# 2022-LC-MNT-3.net
KiCad netlist of a schematic drawn in EasyEDA Pro
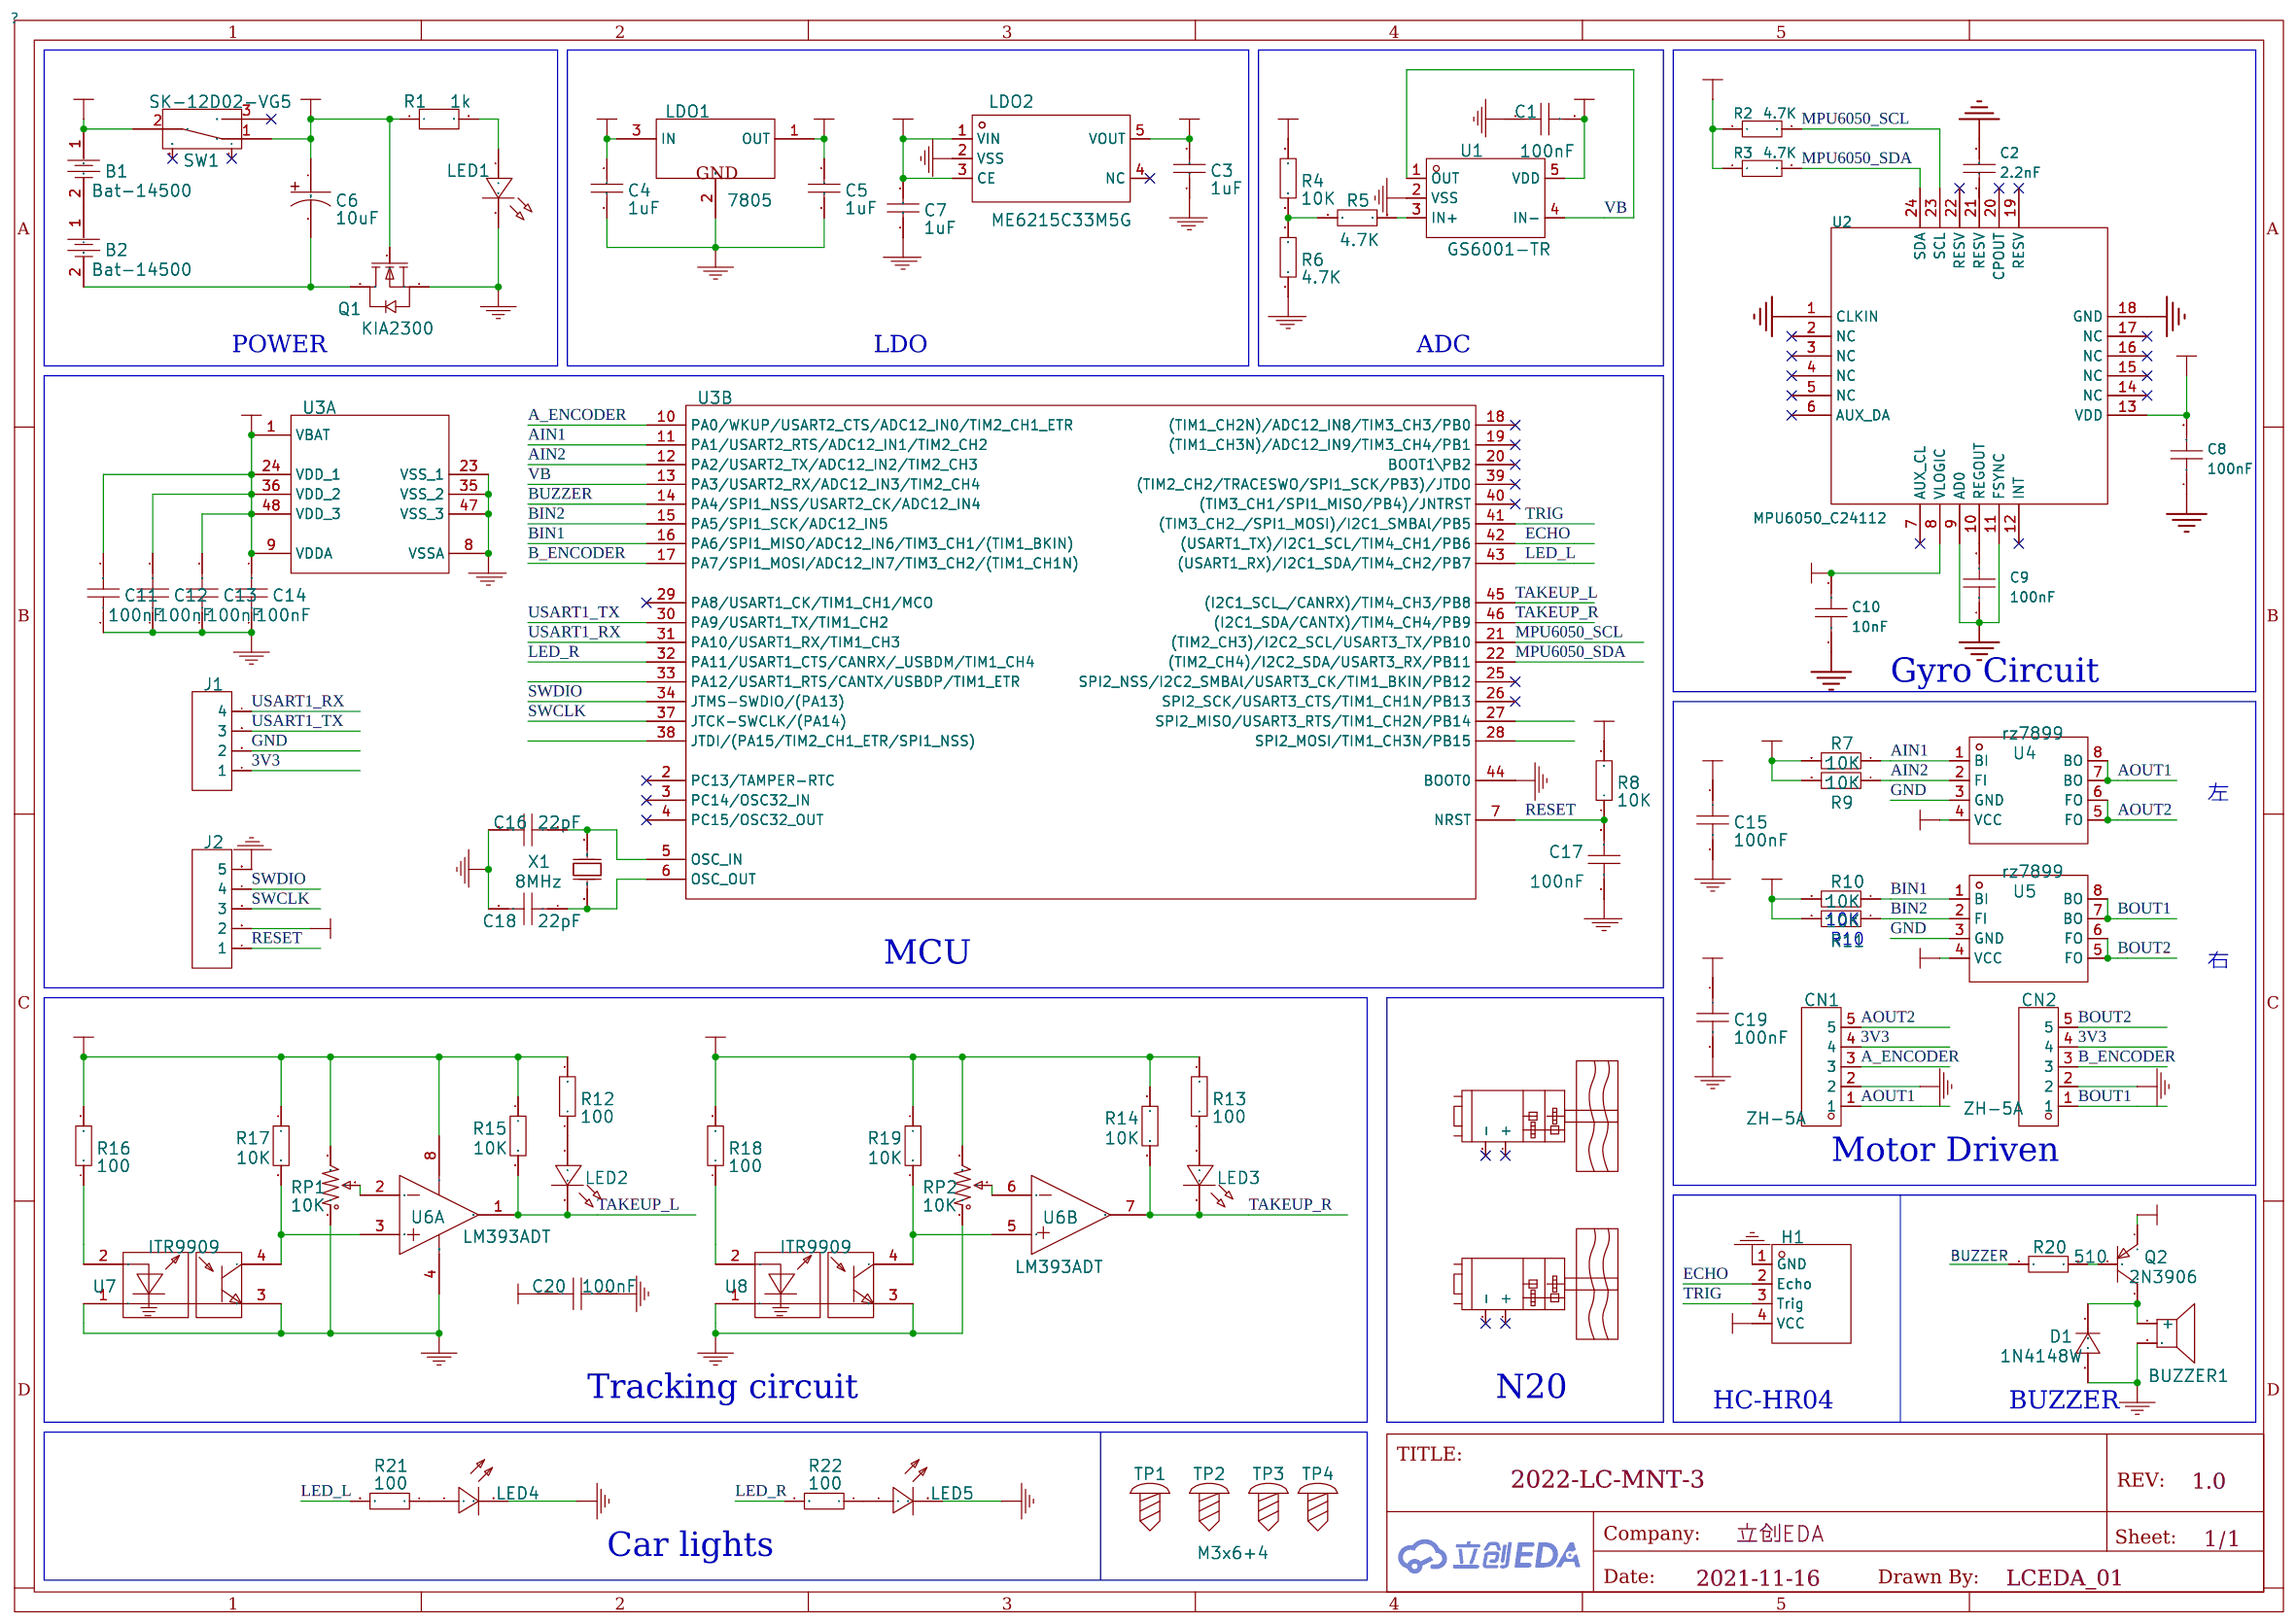
[diagram p0: schematic sheet]

(export (version "E")
  (design (tool "Eeschema 10.0.6"))
  (components
    (comp (ref "ASS_1") (value "直流电机N20") (libsource (lib "easyedapro") (part "直流电机N20")))
    (comp (ref "ASS_2") (value "直流电机N20") (libsource (lib "easyedapro") (part "直流电机N20")))
    (comp (ref "B1") (value "Bat-14500") (libsource (lib "easyedapro") (part "Bat-14500")))
    (comp (ref "B2") (value "Bat-14500") (libsource (lib "easyedapro") (part "Bat-14500")))
    (comp (ref "BUZZER1")
      (value "TMB12A12")
      (fields (field (name "Manufacturer") "HNDZ"))
      (libsource (lib "easyedapro") (part "TMB12A12"))
    )
    (comp (ref "C1")
      (value "100nF")
      (fields (field (name "Manufacturer Part") "CC0603KRX7R9BB104") (field (name "Manufacturer") "YAGEO"))
      (libsource (lib "") (part "100nF_1"))
    )
    (comp (ref "C2") (value "2.2nF") (libsource (lib "easyedapro") (part "2.2nF")))
    (comp (ref "C3")
      (value "1uF")
      (fields (field (name "Manufacturer Part") "CC0603KRX5R8BB105") (field (name "Manufacturer") "YAGEO"))
      (libsource (lib "easyedapro") (part "1uF"))
    )
    (comp (ref "C4")
      (value "1uF")
      (fields (field (name "Manufacturer Part") "CC0603KRX5R8BB105") (field (name "Manufacturer") "YAGEO"))
      (libsource (lib "easyedapro") (part "1uF"))
    )
    (comp (ref "C5")
      (value "1uF")
      (fields (field (name "Manufacturer Part") "CC0603KRX5R8BB105") (field (name "Manufacturer") "YAGEO"))
      (libsource (lib "easyedapro") (part "1uF"))
    )
    (comp (ref "C6")
      (value "10uF")
      (fields (field (name "Manufacturer Part") "CA45-A-16V-10μF-K") (field (name "Manufacturer") "TORCH"))
      (libsource (lib "easyedapro") (part "10uF"))
    )
    (comp (ref "C7")
      (value "1uF")
      (fields (field (name "Manufacturer Part") "CC0603KRX5R8BB105") (field (name "Manufacturer") "YAGEO"))
      (libsource (lib "easyedapro") (part "1uF"))
    )
    (comp (ref "C8") (value "100nF") (libsource (lib "easyedapro") (part "100nF")))
    (comp (ref "C9") (value "100nF") (libsource (lib "easyedapro") (part "100nF")))
    (comp (ref "C10") (value "10nF") (libsource (lib "easyedapro") (part "10nF")))
    (comp (ref "C11")
      (value "100nF")
      (fields (field (name "Manufacturer Part") "CC0603KRX7R9BB104") (field (name "Manufacturer") "YAGEO"))
      (libsource (lib "") (part "100nF_1"))
    )
    (comp (ref "C12")
      (value "100nF")
      (fields (field (name "Manufacturer Part") "CC0603KRX7R9BB104") (field (name "Manufacturer") "YAGEO"))
      (libsource (lib "") (part "100nF_1"))
    )
    (comp (ref "C13")
      (value "100nF")
      (fields (field (name "Manufacturer Part") "CC0603KRX7R9BB104") (field (name "Manufacturer") "YAGEO"))
      (libsource (lib "") (part "100nF_1"))
    )
    (comp (ref "C14")
      (value "100nF")
      (fields (field (name "Manufacturer Part") "CC0603KRX7R9BB104") (field (name "Manufacturer") "YAGEO"))
      (libsource (lib "") (part "100nF_1"))
    )
    (comp (ref "C15")
      (value "100nF")
      (fields (field (name "Manufacturer Part") "CC0603KRX7R9BB104") (field (name "Manufacturer") "YAGEO"))
      (libsource (lib "") (part "100nF_1"))
    )
    (comp (ref "C16")
      (value "22pF")
      (fields (field (name "Manufacturer Part") "CC0603FRNPO9BN220") (field (name "Manufacturer") "YAGEO"))
      (libsource (lib "easyedapro") (part "22pF"))
    )
    (comp (ref "C17")
      (value "100nF")
      (fields (field (name "Manufacturer Part") "CC0603KRX7R9BB104") (field (name "Manufacturer") "YAGEO"))
      (libsource (lib "") (part "100nF_1"))
    )
    (comp (ref "C18")
      (value "22pF")
      (fields (field (name "Manufacturer Part") "CC0603FRNPO9BN220") (field (name "Manufacturer") "YAGEO"))
      (libsource (lib "easyedapro") (part "22pF"))
    )
    (comp (ref "C19")
      (value "100nF")
      (fields (field (name "Manufacturer Part") "CC0603KRX7R9BB104") (field (name "Manufacturer") "YAGEO"))
      (libsource (lib "") (part "100nF_1"))
    )
    (comp (ref "C20")
      (value "100nF")
      (fields (field (name "Manufacturer Part") "CC0603KRX7R9BB104") (field (name "Manufacturer") "YAGEO"))
      (libsource (lib "") (part "100nF_1"))
    )
    (comp (ref "CN1")
      (value "ZH-5A")
      (fields (field (name "Manufacturer") "BOOMELE"))
      (libsource (lib "easyedapro") (part "ZH-5A"))
    )
    (comp (ref "CN2")
      (value "ZH-5A")
      (fields (field (name "Manufacturer") "BOOMELE"))
      (libsource (lib "easyedapro") (part "ZH-5A"))
    )
    (comp (ref "D1")
      (value "1N4148W")
      (fields (field (name "Manufacturer") "Tak Cheong"))
      (libsource (lib "easyedapro") (part "1N4148W"))
    )
    (comp (ref "H1") (value "超声波测距模块_HC-HR04") (libsource (lib "easyedapro") (part "超声波测距模块_HC-HR04")))
    (comp (ref "J1") (value "HDR-M-2.54_1x4") (libsource (lib "easyedapro") (part "HDR-M-2.54_1x4")))
    (comp (ref "J2") (value "HDR-M-2.54_1x5") (libsource (lib "easyedapro") (part "HDR-M-2.54_1x5")))
    (comp (ref "LDO1")
      (value "7805")
      (fields (field (name "Manufacturer Part") "CJ78L05") (field (name "Manufacturer") "CJ"))
      (libsource (lib "easyedapro") (part "7805"))
    )
    (comp (ref "LDO2")
      (value "ME6215C33M5G")
      (fields (field (name "Manufacturer") "MICRONE"))
      (libsource (lib "easyedapro") (part "ME6215C33M5G"))
    )
    (comp (ref "LED1")
      (value "LED-0603_R")
      (fields
        (field (name "Manufacturer Part") "19-217/R6C-AL1M2VY/3T")
        (field (name "Manufacturer") "EVERLIGHT(台湾亿光)")
      )
      (libsource (lib "easyedapro") (part "LED-0603_R"))
    )
    (comp (ref "LED2")
      (value "LED-0805_G")
      (fields (field (name "Manufacturer Part") "NCD0805G1") (field (name "Manufacturer") "国星光电"))
      (libsource (lib "easyedapro") (part "LED-0805_G"))
    )
    (comp (ref "LED3")
      (value "LED-0805_G")
      (fields (field (name "Manufacturer Part") "NCD0805G1") (field (name "Manufacturer") "国星光电"))
      (libsource (lib "easyedapro") (part "LED-0805_G"))
    )
    (comp (ref "LED4")
      (value "TJ-L5FCMYGTDLSFLC6TW-A5")
      (fields (field (name "Manufacturer") "TOGIALED"))
      (libsource (lib "easyedapro") (part "TJ-L5FCMYGTDLSFLC6TW-A5"))
    )
    (comp (ref "LED5")
      (value "TJ-L5FCMYGTDLSFLC6TW-A5")
      (fields (field (name "Manufacturer") "TOGIALED"))
      (libsource (lib "easyedapro") (part "TJ-L5FCMYGTDLSFLC6TW-A5"))
    )
    (comp (ref "Q1")
      (value "KIA2300")
      (fields (field (name "Manufacturer") "KIA"))
      (libsource (lib "easyedapro") (part "KIA2300"))
    )
    (comp (ref "Q2")
      (value "2N3906")
      (fields (field (name "Manufacturer Part") "2N3906S-RTK/PS") (field (name "Manufacturer") "KEC"))
      (libsource (lib "easyedapro") (part "2N3906"))
    )
    (comp (ref "R1") (value "1k") (libsource (lib "easyedapro") (part "1k")))
    (comp (ref "R2") (value "4.7K") (libsource (lib "") (part "4.7K_1")))
    (comp (ref "R3") (value "4.7K") (libsource (lib "") (part "4.7K_1")))
    (comp (ref "R4")
      (value "10K")
      (fields (field (name "Manufacturer Part") "AR03BTCX1002") (field (name "Manufacturer") "Viking Tech"))
      (libsource (lib "easyedapro") (part "10K"))
    )
    (comp (ref "R5")
      (value "4.7K")
      (fields (field (name "Manufacturer Part") "RS-03K4701FT") (field (name "Manufacturer") "FH"))
      (libsource (lib "easyedapro") (part "4.7K"))
    )
    (comp (ref "R6")
      (value "4.7K")
      (fields (field (name "Manufacturer Part") "RS-03K4701FT") (field (name "Manufacturer") "FH"))
      (libsource (lib "easyedapro") (part "4.7K"))
    )
    (comp (ref "R7")
      (value "10K")
      (fields (field (name "Manufacturer Part") "AR03BTCX1002") (field (name "Manufacturer") "Viking Tech"))
      (libsource (lib "easyedapro") (part "10K"))
    )
    (comp (ref "R8")
      (value "10K")
      (fields (field (name "Manufacturer Part") "AR03BTCX1002") (field (name "Manufacturer") "Viking Tech"))
      (libsource (lib "easyedapro") (part "10K"))
    )
    (comp (ref "R9")
      (value "10K")
      (fields (field (name "Manufacturer Part") "AR03BTCX1002") (field (name "Manufacturer") "Viking Tech"))
      (libsource (lib "easyedapro") (part "10K"))
    )
    (comp (ref "R10")
      (value "10K")
      (fields (field (name "Manufacturer Part") "AR03BTCX1002") (field (name "Manufacturer") "Viking Tech"))
      (libsource (lib "easyedapro") (part "10K"))
    )
    (comp (ref "R11")
      (value "10K")
      (fields (field (name "Manufacturer Part") "AR03BTCX1002") (field (name "Manufacturer") "Viking Tech"))
      (libsource (lib "easyedapro") (part "10K"))
    )
    (comp (ref "R12")
      (value "100")
      (fields (field (name "Manufacturer Part") "RS-03K101JT") (field (name "Manufacturer") "FH"))
      (libsource (lib "easyedapro") (part "100"))
    )
    (comp (ref "R13")
      (value "100")
      (fields (field (name "Manufacturer Part") "RS-03K101JT") (field (name "Manufacturer") "FH"))
      (libsource (lib "easyedapro") (part "100"))
    )
    (comp (ref "R14")
      (value "10K")
      (fields (field (name "Manufacturer Part") "AR03BTCX1002") (field (name "Manufacturer") "Viking Tech"))
      (libsource (lib "easyedapro") (part "10K"))
    )
    (comp (ref "R15")
      (value "10K")
      (fields (field (name "Manufacturer Part") "AR03BTCX1002") (field (name "Manufacturer") "Viking Tech"))
      (libsource (lib "easyedapro") (part "10K"))
    )
    (comp (ref "R16")
      (value "100")
      (fields (field (name "Manufacturer Part") "RS-03K101JT") (field (name "Manufacturer") "FH"))
      (libsource (lib "easyedapro") (part "100"))
    )
    (comp (ref "R17")
      (value "10K")
      (fields (field (name "Manufacturer Part") "AR03BTCX1002") (field (name "Manufacturer") "Viking Tech"))
      (libsource (lib "easyedapro") (part "10K"))
    )
    (comp (ref "R18")
      (value "100")
      (fields (field (name "Manufacturer Part") "RS-03K101JT") (field (name "Manufacturer") "FH"))
      (libsource (lib "easyedapro") (part "100"))
    )
    (comp (ref "R19")
      (value "10K")
      (fields (field (name "Manufacturer Part") "AR03BTCX1002") (field (name "Manufacturer") "Viking Tech"))
      (libsource (lib "easyedapro") (part "10K"))
    )
    (comp (ref "R20")
      (value "510")
      (fields (field (name "Manufacturer Part") "ERJUP3J511V") (field (name "Manufacturer") "PANASONIC"))
      (libsource (lib "easyedapro") (part "510"))
    )
    (comp (ref "R21")
      (value "100")
      (fields (field (name "Manufacturer Part") "RS-03K101JT") (field (name "Manufacturer") "FH"))
      (libsource (lib "easyedapro") (part "100"))
    )
    (comp (ref "R22")
      (value "100")
      (fields (field (name "Manufacturer Part") "RS-03K101JT") (field (name "Manufacturer") "FH"))
      (libsource (lib "easyedapro") (part "100"))
    )
    (comp (ref "RP1") (value "10K") (libsource (lib "") (part "10K_1")))
    (comp (ref "RP2") (value "10K") (libsource (lib "") (part "10K_1")))
    (comp (ref "SW1")
      (value "SK-12D02-VG5")
      (fields (field (name "Manufacturer") "Rectangular Connectors - Contacts"))
      (libsource (lib "easyedapro") (part "SK-12D02-VG5"))
    )
    (comp (ref "TP1") (value "M3x6+4") (libsource (lib "easyedapro") (part "M3x6+4")))
    (comp (ref "TP2") (value "M3x6+4") (libsource (lib "easyedapro") (part "M3x6+4")))
    (comp (ref "TP3") (value "M3x6+4") (libsource (lib "easyedapro") (part "M3x6+4")))
    (comp (ref "TP4") (value "M3x6+4") (libsource (lib "easyedapro") (part "M3x6+4")))
    (comp (ref "U1")
      (value "GS6001-TR")
      (fields (field (name "Manufacturer") "Gainsil"))
      (libsource (lib "easyedapro") (part "GS6001-TR"))
    )
    (comp (ref "U2") (value "MPU6050_C24112") (libsource (lib "easyedapro") (part "MPU-6050_C24112")))
    (comp (ref "U3") (value "STM32F103C8T6") (libsource (lib "easyedapro") (part "STM32F103C8T6")))
    (comp (ref "U4")
      (value "rz7899")
      (fields (field (name "Manufacturer") "RZ"))
      (libsource (lib "easyedapro") (part "rz7899"))
    )
    (comp (ref "U5")
      (value "rz7899")
      (fields (field (name "Manufacturer") "RZ"))
      (libsource (lib "easyedapro") (part "rz7899"))
    )
    (comp (ref "U6")
      (value "LM393ADT")
      (fields (field (name "Manufacturer") "STMicroelectronics"))
      (libsource (lib "easyedapro") (part "LM393ADT"))
    )
    (comp (ref "U7")
      (value "ITR9909")
      (fields (field (name "Manufacturer") "EVERLIGHT"))
      (libsource (lib "easyedapro") (part "ITR9909"))
    )
    (comp (ref "U8")
      (value "ITR9909")
      (fields (field (name "Manufacturer") "EVERLIGHT"))
      (libsource (lib "easyedapro") (part "ITR9909"))
    )
    (comp (ref "X1")
      (value "8MHz")
      (fields (field (name "Manufacturer Part") "X50328MSB2GI") (field (name "Manufacturer") "YXC"))
      (libsource (lib "easyedapro") (part "8MHz"))
    )
  )
  (nets
    (net (code "1") (name "+5V") (class "Default")
      (node (ref "C5") (pin "2") (pinfunction "2_2") (pintype "input"))
      (node (ref "C7") (pin "2") (pinfunction "2_2") (pintype "input"))
      (node (ref "H1") (pin "4") (pinfunction "VCC_4") (pintype "input"))
      (node (ref "LDO1") (pin "1") (pinfunction "OUT_1") (pintype "input"))
      (node (ref "LDO2") (pin "1") (pinfunction "VIN_1") (pintype "input"))
      (node (ref "LDO2") (pin "3") (pinfunction "CE_3") (pintype "input"))
    )
    (net (code "2") (name "/AIN1") (class "Default")
      (node (ref "R7") (pin "1") (pinfunction "1_1") (pintype "input"))
      (node (ref "U3") (pin "11") (pinfunction "PA1/USART2_RTS/ADC12_IN1/TIM2_CH2_11") (pintype "bidirectional"))
      (node (ref "U4") (pin "1") (pinfunction "BI_1") (pintype "input"))
    )
    (net (code "3") (name "/AIN2") (class "Default")
      (node (ref "R9") (pin "1") (pinfunction "1_1") (pintype "input"))
      (node (ref "U3") (pin "12") (pinfunction "PA2/USART2_TX/ADC12_IN2/TIM2_CH3_12") (pintype "bidirectional"))
      (node (ref "U4") (pin "2") (pinfunction "FI_2") (pintype "input"))
    )
    (net (code "4") (name "/AOUT1") (class "Default")
      (node (ref "CN1") (pin "1") (pinfunction "1_1") (pintype "input"))
      (node (ref "U4") (pin "7") (pinfunction "BO_7") (pintype "input"))
      (node (ref "U4") (pin "8") (pinfunction "BO_8") (pintype "input"))
    )
    (net (code "5") (name "/AOUT2") (class "Default")
      (node (ref "CN1") (pin "5") (pinfunction "5_5") (pintype "input"))
      (node (ref "U4") (pin "5") (pinfunction "FO_5") (pintype "input"))
      (node (ref "U4") (pin "6") (pinfunction "FO_6") (pintype "input"))
    )
    (net (code "6") (name "/A_ENCODER") (class "Default")
      (node (ref "CN1") (pin "3") (pinfunction "3_3") (pintype "input"))
      (node (ref "U3") (pin "10") (pinfunction "PA0/WKUP/USART2_CTS/ADC12_IN0/TIM2_CH1_ETR_10") (pintype "bidirectional"))
    )
    (net (code "7") (name "/BIN1") (class "Default")
      (node (ref "R10") (pin "1") (pinfunction "1_1") (pintype "input"))
      (node (ref "U3") (pin "16") (pinfunction "PA6/SPI1_MISO/ADC12_IN6/TIM3_CH1/(TIM1_BKIN)_16") (pintype "bidirectional"))
      (node (ref "U5") (pin "1") (pinfunction "BI_1") (pintype "input"))
    )
    (net (code "8") (name "/BIN2") (class "Default")
      (node (ref "R11") (pin "1") (pinfunction "1_1") (pintype "input"))
      (node (ref "U3") (pin "15") (pinfunction "PA5/SPI1_SCK/ADC12_IN5_15") (pintype "bidirectional"))
      (node (ref "U5") (pin "2") (pinfunction "FI_2") (pintype "input"))
    )
    (net (code "9") (name "/BOUT1") (class "Default")
      (node (ref "CN2") (pin "1") (pinfunction "1_1") (pintype "input"))
      (node (ref "U5") (pin "7") (pinfunction "BO_7") (pintype "input"))
      (node (ref "U5") (pin "8") (pinfunction "BO_8") (pintype "input"))
    )
    (net (code "10") (name "/BOUT2") (class "Default")
      (node (ref "CN2") (pin "5") (pinfunction "5_5") (pintype "input"))
      (node (ref "U5") (pin "5") (pinfunction "FO_5") (pintype "input"))
      (node (ref "U5") (pin "6") (pinfunction "FO_6") (pintype "input"))
    )
    (net (code "11") (name "/BUZZER") (class "Default")
      (node (ref "R20") (pin "1") (pinfunction "1_1") (pintype "input"))
      (node (ref "U3") (pin "14") (pinfunction "PA4/SPI1_NSS/USART2_CK/ADC12_IN4_14") (pintype "bidirectional"))
    )
    (net (code "12") (name "/B_ENCODER") (class "Default")
      (node (ref "CN2") (pin "3") (pinfunction "3_3") (pintype "input"))
      (node (ref "U3") (pin "17") (pinfunction "PA7/SPI1_MOSI/ADC12_IN7/TIM3_CH2/(TIM1_CH1N)_17") (pintype "bidirectional"))
    )
    (net (code "13") (name "/ECHO") (class "Default")
      (node (ref "H1") (pin "2") (pinfunction "Echo_2") (pintype "input"))
      (node (ref "U3") (pin "42") (pinfunction "(USART1_TX)/I2C1_SCL/TIM4_CH1/PB6_42") (pintype "bidirectional"))
    )
    (net (code "14") (name "/LED_L") (class "Default")
      (node (ref "R21") (pin "2") (pinfunction "2_2") (pintype "input"))
      (node (ref "U3") (pin "43") (pinfunction "(USART1_RX)/I2C1_SDA/TIM4_CH2/PB7_43") (pintype "bidirectional"))
    )
    (net (code "15") (name "/LED_R") (class "Default")
      (node (ref "R22") (pin "2") (pinfunction "2_2") (pintype "input"))
      (node (ref "U3") (pin "32") (pinfunction "PA11/USART1_CTS/CANRX/_USBDM/TIM1_CH4_32") (pintype "bidirectional"))
    )
    (net (code "16") (name "/MPU6050_SCL") (class "Default")
      (node (ref "R2") (pin "2") (pinfunction "2_2") (pintype "input"))
      (node (ref "U2") (pin "23") (pinfunction "SCL_23") (pintype "input"))
      (node (ref "U3") (pin "21") (pinfunction "(TIM2_CH3)/I2C2_SCL/USART3_TX/PB10_21") (pintype "bidirectional"))
    )
    (net (code "17") (name "/MPU6050_SDA") (class "Default")
      (node (ref "R3") (pin "2") (pinfunction "2_2") (pintype "input"))
      (node (ref "U2") (pin "24") (pinfunction "SDA_24") (pintype "input"))
      (node (ref "U3") (pin "22") (pinfunction "(TIM2_CH4)/I2C2_SDA/USART3_RX/PB11_22") (pintype "bidirectional"))
    )
    (net (code "18") (name "/RESET") (class "Default")
      (node (ref "C17") (pin "2") (pinfunction "2_2") (pintype "input"))
      (node (ref "J2") (pin "1") (pinfunction "1_1") (pintype "input"))
      (node (ref "R8") (pin "1") (pinfunction "1_1") (pintype "input"))
      (node (ref "U3") (pin "7") (pinfunction "NRST_7") (pintype "bidirectional"))
    )
    (net (code "19") (name "/SWCLK") (class "Default")
      (node (ref "J2") (pin "3") (pinfunction "3_3") (pintype "input"))
      (node (ref "U3") (pin "37") (pinfunction "JTCK-SWCLK/(PA14)_37") (pintype "bidirectional"))
    )
    (net (code "20") (name "/SWDIO") (class "Default")
      (node (ref "J2") (pin "4") (pinfunction "4_4") (pintype "input"))
      (node (ref "U3") (pin "34") (pinfunction "JTMS-SWDIO/(PA13)_34") (pintype "bidirectional"))
    )
    (net (code "21") (name "/TAKEUP_L") (class "Default")
      (node (ref "LED2") (pin "2") (pinfunction "2_2") (pintype "input"))
      (node (ref "R15") (pin "2") (pinfunction "2_2") (pintype "input"))
      (node (ref "U3") (pin "45") (pinfunction "(I2C1_SCL_/CANRX)/TIM4_CH3/PB8_45") (pintype "bidirectional"))
      (node (ref "U6") (pin "1") (pinfunction "OUT_1") (pintype "output"))
    )
    (net (code "22") (name "/TAKEUP_R") (class "Default")
      (node (ref "LED3") (pin "2") (pinfunction "2_2") (pintype "input"))
      (node (ref "R14") (pin "2") (pinfunction "2_2") (pintype "input"))
      (node (ref "U3") (pin "46") (pinfunction "(I2C1_SDA/CANTX)/TIM4_CH4/PB9_46") (pintype "bidirectional"))
      (node (ref "U6") (pin "7") (pinfunction "OUT_7") (pintype "output"))
    )
    (net (code "23") (name "/TRIG") (class "Default")
      (node (ref "H1") (pin "3") (pinfunction "Trig_3") (pintype "input"))
      (node (ref "U3") (pin "41") (pinfunction "(TIM3_CH2_/SPI1_MOSI)/I2C1_SMBAl/PB5_41") (pintype "bidirectional"))
    )
    (net (code "24") (name "/USART1_RX") (class "Default")
      (node (ref "J1") (pin "4") (pinfunction "4_4") (pintype "input"))
      (node (ref "U3") (pin "31") (pinfunction "PA10/USART1_RX/TIM1_CH3_31") (pintype "bidirectional"))
    )
    (net (code "25") (name "/USART1_TX") (class "Default")
      (node (ref "J1") (pin "3") (pinfunction "3_3") (pintype "input"))
      (node (ref "U3") (pin "30") (pinfunction "PA9/USART1_TX/TIM1_CH2_30") (pintype "bidirectional"))
    )
    (net (code "26") (name "/VB") (class "Default")
      (node (ref "U1") (pin "1") (pinfunction "OUT_1") (pintype "input"))
      (node (ref "U1") (pin "4") (pinfunction "IN-_4") (pintype "input"))
      (node (ref "U3") (pin "13") (pinfunction "PA3/USART2_RX/ADC12_IN3/TIM2_CH4_13") (pintype "bidirectional"))
    )
    (net (code "27") (name "3V3") (class "Default")
      (node (ref "C1") (pin "2") (pinfunction "2_2") (pintype "input"))
      (node (ref "C10") (pin "2") (pinfunction "2_2") (pintype "input"))
      (node (ref "C11") (pin "2") (pinfunction "2_2") (pintype "input"))
      (node (ref "C12") (pin "2") (pinfunction "2_2") (pintype "input"))
      (node (ref "C13") (pin "2") (pinfunction "2_2") (pintype "input"))
      (node (ref "C14") (pin "2") (pinfunction "2_2") (pintype "input"))
      (node (ref "C20") (pin "1") (pinfunction "1_1") (pintype "input"))
      (node (ref "C3") (pin "2") (pinfunction "2_2") (pintype "input"))
      (node (ref "C8") (pin "2") (pinfunction "2_2") (pintype "input"))
      (node (ref "CN1") (pin "4") (pinfunction "4_4") (pintype "input"))
      (node (ref "CN2") (pin "4") (pinfunction "4_4") (pintype "input"))
      (node (ref "J1") (pin "1") (pinfunction "1_1") (pintype "input"))
      (node (ref "J2") (pin "2") (pinfunction "2_2") (pintype "input"))
      (node (ref "LDO2") (pin "5") (pinfunction "VOUT_5") (pintype "input"))
      (node (ref "Q2") (pin "1") (pinfunction "E_1") (pintype "input"))
      (node (ref "R10") (pin "2") (pinfunction "2_2") (pintype "input"))
      (node (ref "R11") (pin "2") (pinfunction "2_2") (pintype "input"))
      (node (ref "R12") (pin "2") (pinfunction "2_2") (pintype "input"))
      (node (ref "R13") (pin "2") (pinfunction "2_2") (pintype "input"))
      (node (ref "R14") (pin "1") (pinfunction "1_1") (pintype "input"))
      (node (ref "R15") (pin "1") (pinfunction "1_1") (pintype "input"))
      (node (ref "R16") (pin "2") (pinfunction "2_2") (pintype "input"))
      (node (ref "R17") (pin "1") (pinfunction "1_1") (pintype "input"))
      (node (ref "R18") (pin "2") (pinfunction "2_2") (pintype "input"))
      (node (ref "R19") (pin "1") (pinfunction "1_1") (pintype "input"))
      (node (ref "R2") (pin "1") (pinfunction "1_1") (pintype "input"))
      (node (ref "R3") (pin "1") (pinfunction "1_1") (pintype "input"))
      (node (ref "R7") (pin "2") (pinfunction "2_2") (pintype "input"))
      (node (ref "R8") (pin "2") (pinfunction "2_2") (pintype "input"))
      (node (ref "R9") (pin "2") (pinfunction "2_2") (pintype "input"))
      (node (ref "RP1") (pin "3") (pinfunction "3_3") (pintype "input"))
      (node (ref "RP2") (pin "3") (pinfunction "3_3") (pintype "input"))
      (node (ref "U1") (pin "5") (pinfunction "VDD_5") (pintype "input"))
      (node (ref "U2") (pin "13") (pinfunction "VDD_13") (pintype "input"))
      (node (ref "U2") (pin "8") (pinfunction "VLOGIC_8") (pintype "input"))
      (node (ref "U3") (pin "1") (pinfunction "VBAT_1") (pintype "input"))
      (node (ref "U3") (pin "24") (pinfunction "VDD_1_24") (pintype "input"))
      (node (ref "U3") (pin "36") (pinfunction "VDD_2_36") (pintype "input"))
      (node (ref "U3") (pin "48") (pinfunction "VDD_3_48") (pintype "input"))
      (node (ref "U3") (pin "9") (pinfunction "VDDA_9") (pintype "input"))
      (node (ref "U6") (pin "8") (pinfunction "V+_8") (pintype "input"))
    )
    (net (code "28") (name "GND") (class "Default")
      (node (ref "BUZZER1") (pin "2") (pinfunction "2_2") (pintype "input"))
      (node (ref "C1") (pin "1") (pinfunction "1_1") (pintype "input"))
      (node (ref "C10") (pin "1") (pinfunction "1_1") (pintype "input"))
      (node (ref "C11") (pin "1") (pinfunction "1_1") (pintype "input"))
      (node (ref "C12") (pin "1") (pinfunction "1_1") (pintype "input"))
      (node (ref "C13") (pin "1") (pinfunction "1_1") (pintype "input"))
      (node (ref "C14") (pin "1") (pinfunction "1_1") (pintype "input"))
      (node (ref "C15") (pin "2") (pinfunction "2_2") (pintype "input"))
      (node (ref "C16") (pin "2") (pinfunction "2_2") (pintype "input"))
      (node (ref "C17") (pin "1") (pinfunction "1_1") (pintype "input"))
      (node (ref "C18") (pin "2") (pinfunction "2_2") (pintype "input"))
      (node (ref "C19") (pin "2") (pinfunction "2_2") (pintype "input"))
      (node (ref "C2") (pin "2") (pinfunction "2_2") (pintype "input"))
      (node (ref "C20") (pin "2") (pinfunction "2_2") (pintype "input"))
      (node (ref "C3") (pin "1") (pinfunction "1_1") (pintype "input"))
      (node (ref "C4") (pin "1") (pinfunction "1_1") (pintype "input"))
      (node (ref "C5") (pin "1") (pinfunction "1_1") (pintype "input"))
      (node (ref "C7") (pin "1") (pinfunction "1_1") (pintype "input"))
      (node (ref "C8") (pin "1") (pinfunction "1_1") (pintype "input"))
      (node (ref "C9") (pin "1") (pinfunction "1_1") (pintype "input"))
      (node (ref "CN1") (pin "2") (pinfunction "2_2") (pintype "input"))
      (node (ref "CN2") (pin "2") (pinfunction "2_2") (pintype "input"))
      (node (ref "D1") (pin "2") (pinfunction "2_2") (pintype "input"))
      (node (ref "H1") (pin "1") (pinfunction "GND_1") (pintype "input"))
      (node (ref "J1") (pin "2") (pinfunction "2_2") (pintype "input"))
      (node (ref "J2") (pin "5") (pinfunction "5_5") (pintype "input"))
      (node (ref "LDO1") (pin "2") (pinfunction "GND_2") (pintype "input"))
      (node (ref "LDO2") (pin "2") (pinfunction "VSS_2") (pintype "input"))
      (node (ref "LED1") (pin "2") (pinfunction "2_2") (pintype "input"))
      (node (ref "LED4") (pin "2") (pinfunction "2_2") (pintype "input"))
      (node (ref "LED5") (pin "2") (pinfunction "2_2") (pintype "input"))
      (node (ref "Q1") (pin "2") (pinfunction "S_2") (pintype "input"))
      (node (ref "R6") (pin "1") (pinfunction "1_1") (pintype "input"))
      (node (ref "RP1") (pin "1") (pinfunction "1_1") (pintype "input"))
      (node (ref "RP2") (pin "1") (pinfunction "1_1") (pintype "input"))
      (node (ref "U1") (pin "2") (pinfunction "VSS_2") (pintype "input"))
      (node (ref "U2") (pin "1") (pinfunction "CLKIN_1") (pintype "input"))
      (node (ref "U2") (pin "11") (pinfunction "FSYNC_11") (pintype "input"))
      (node (ref "U2") (pin "18") (pinfunction "GND_18") (pintype "input"))
      (node (ref "U2") (pin "9") (pinfunction "AD0_9") (pintype "input"))
      (node (ref "U3") (pin "23") (pinfunction "VSS_1_23") (pintype "input"))
      (node (ref "U3") (pin "35") (pinfunction "VSS_2_35") (pintype "input"))
      (node (ref "U3") (pin "44") (pinfunction "BOOT0_44") (pintype "input"))
      (node (ref "U3") (pin "47") (pinfunction "VSS_3_47") (pintype "input"))
      (node (ref "U3") (pin "8") (pinfunction "VSSA_8") (pintype "input"))
      (node (ref "U4") (pin "3") (pinfunction "GND_3") (pintype "input"))
      (node (ref "U5") (pin "3") (pinfunction "GND_3") (pintype "input"))
      (node (ref "U6") (pin "4") (pinfunction "GND_4") (pintype "input"))
      (node (ref "U7") (pin "1") (pinfunction "1_1") (pintype "input"))
      (node (ref "U7") (pin "3") (pinfunction "3_3") (pintype "input"))
      (node (ref "U8") (pin "1") (pinfunction "1_1") (pintype "input"))
      (node (ref "U8") (pin "3") (pinfunction "3_3") (pintype "input"))
    )
    (net (code "29") (name "Net-(B1-Pad2)") (class "Default")
      (node (ref "B1") (pin "2") (pinfunction "2_2") (pintype "input"))
      (node (ref "B2") (pin "1") (pinfunction "1_1") (pintype "input"))
    )
    (net (code "30") (name "Net-(BUZZER1-+)") (class "Default")
      (node (ref "BUZZER1") (pin "1") (pinfunction "+_1") (pintype "input"))
      (node (ref "D1") (pin "1") (pinfunction "1_1") (pintype "input"))
      (node (ref "Q2") (pin "3") (pinfunction "C_3") (pintype "input"))
    )
    (net (code "31") (name "Net-(C2-Pad1)") (class "Default")
      (node (ref "C2") (pin "1") (pinfunction "1_1") (pintype "input"))
      (node (ref "U2") (pin "21") (pinfunction "RESV_21") (pintype "input"))
    )
    (net (code "32") (name "Net-(LED1-Pad1)") (class "Default")
      (node (ref "LED1") (pin "1") (pinfunction "1_1") (pintype "input"))
      (node (ref "R1") (pin "2") (pinfunction "2_2") (pintype "input"))
    )
    (net (code "33") (name "Net-(LED2-Pad1)") (class "Default")
      (node (ref "LED2") (pin "1") (pinfunction "1_1") (pintype "input"))
      (node (ref "R12") (pin "1") (pinfunction "1_1") (pintype "input"))
    )
    (net (code "34") (name "Net-(LED3-Pad1)") (class "Default")
      (node (ref "LED3") (pin "1") (pinfunction "1_1") (pintype "input"))
      (node (ref "R13") (pin "1") (pinfunction "1_1") (pintype "input"))
    )
    (net (code "35") (name "Net-(LED4-Pad1)") (class "Default")
      (node (ref "LED4") (pin "1") (pinfunction "1_1") (pintype "input"))
      (node (ref "R21") (pin "1") (pinfunction "1_1") (pintype "input"))
    )
    (net (code "36") (name "Net-(LED5-Pad1)") (class "Default")
      (node (ref "LED5") (pin "1") (pinfunction "1_1") (pintype "input"))
      (node (ref "R22") (pin "1") (pinfunction "1_1") (pintype "input"))
    )
    (net (code "37") (name "Net-(Q1-D)") (class "Default")
      (node (ref "B2") (pin "2") (pinfunction "2_2") (pintype "input"))
      (node (ref "C6") (pin "2") (pinfunction "2_2") (pintype "input"))
      (node (ref "Q1") (pin "3") (pinfunction "D_3") (pintype "input"))
    )
    (net (code "38") (name "Net-(Q2-B)") (class "Default")
      (node (ref "Q2") (pin "2") (pinfunction "B_2") (pintype "input"))
      (node (ref "R20") (pin "2") (pinfunction "2_2") (pintype "input"))
    )
    (net (code "39") (name "Net-(R4-Pad2)") (class "Default")
      (node (ref "R4") (pin "2") (pinfunction "2_2") (pintype "input"))
      (node (ref "R5") (pin "1") (pinfunction "1_1") (pintype "input"))
      (node (ref "R6") (pin "2") (pinfunction "2_2") (pintype "input"))
    )
    (net (code "40") (name "Net-(R16-Pad1)") (class "Default")
      (node (ref "R16") (pin "1") (pinfunction "1_1") (pintype "input"))
      (node (ref "U7") (pin "2") (pinfunction "2_2") (pintype "input"))
    )
    (net (code "41") (name "Net-(R18-Pad1)") (class "Default")
      (node (ref "R18") (pin "1") (pinfunction "1_1") (pintype "input"))
      (node (ref "U8") (pin "2") (pinfunction "2_2") (pintype "input"))
    )
    (net (code "42") (name "Net-(U1-IN+)") (class "Default")
      (node (ref "R5") (pin "2") (pinfunction "2_2") (pintype "input"))
      (node (ref "U1") (pin "3") (pinfunction "IN+_3") (pintype "input"))
    )
    (net (code "43") (name "Net-(U2-REGOUT)") (class "Default")
      (node (ref "C9") (pin "2") (pinfunction "2_2") (pintype "input"))
      (node (ref "U2") (pin "10") (pinfunction "REGOUT_10") (pintype "input"))
    )
    (net (code "44") (name "Net-(U3B-OSC_IN)") (class "Default")
      (node (ref "C16") (pin "1") (pinfunction "1_1") (pintype "input"))
      (node (ref "U3") (pin "5") (pinfunction "OSC_IN_5") (pintype "bidirectional"))
      (node (ref "X1") (pin "2") (pinfunction "OSC2_2") (pintype "input"))
    )
    (net (code "45") (name "Net-(U3B-OSC_OUT)") (class "Default")
      (node (ref "C18") (pin "1") (pinfunction "1_1") (pintype "input"))
      (node (ref "U3") (pin "6") (pinfunction "OSC_OUT_6") (pintype "bidirectional"))
      (node (ref "X1") (pin "1") (pinfunction "OSC1_1") (pintype "input"))
    )
    (net (code "46") (name "Net-(U6A-IN+)") (class "Default")
      (node (ref "R17") (pin "2") (pinfunction "2_2") (pintype "input"))
      (node (ref "U6") (pin "3") (pinfunction "IN+_3") (pintype "input"))
      (node (ref "U7") (pin "4") (pinfunction "4_4") (pintype "input"))
    )
    (net (code "47") (name "Net-(U6A-IN-)") (class "Default")
      (node (ref "RP1") (pin "2") (pinfunction "2_2") (pintype "input"))
      (node (ref "U6") (pin "2") (pinfunction "IN-_2") (pintype "input"))
    )
    (net (code "48") (name "Net-(U6B-IN+)") (class "Default")
      (node (ref "R19") (pin "2") (pinfunction "2_2") (pintype "input"))
      (node (ref "U6") (pin "5") (pinfunction "IN+_5") (pintype "input"))
      (node (ref "U8") (pin "4") (pinfunction "4_4") (pintype "input"))
    )
    (net (code "49") (name "Net-(U6B-IN-)") (class "Default")
      (node (ref "RP2") (pin "2") (pinfunction "2_2") (pintype "input"))
      (node (ref "U6") (pin "6") (pinfunction "IN-_6") (pintype "input"))
    )
    (net (code "50") (name "VCC") (class "Default")
      (node (ref "C15") (pin "1") (pinfunction "1_1") (pintype "input"))
      (node (ref "C19") (pin "1") (pinfunction "1_1") (pintype "input"))
      (node (ref "C4") (pin "2") (pinfunction "2_2") (pintype "input"))
      (node (ref "C6") (pin "1") (pinfunction "1_1") (pintype "input"))
      (node (ref "LDO1") (pin "3") (pinfunction "IN_3") (pintype "input"))
      (node (ref "Q1") (pin "1") (pinfunction "G_1") (pintype "input"))
      (node (ref "R1") (pin "1") (pinfunction "1_1") (pintype "input"))
      (node (ref "R4") (pin "1") (pinfunction "1_1") (pintype "input"))
      (node (ref "SW1") (pin "1") (pinfunction "1_1") (pintype "input"))
      (node (ref "U4") (pin "4") (pinfunction "VCC_4") (pintype "input"))
      (node (ref "U5") (pin "4") (pinfunction "VCC_4") (pintype "input"))
    )
    (net (code "51") (name "VCC_IN") (class "Default")
      (node (ref "B1") (pin "1") (pinfunction "1_1") (pintype "input"))
      (node (ref "SW1") (pin "2") (pinfunction "2_2") (pintype "input"))
    )
    (net (code "52") (name "unconnected-(ASS_1-+-Pad1)") (class "Default")
      (node (ref "ASS_1") (pin "1") (pinfunction "+_1") (pintype "input+no_connect"))
    )
    (net (code "53") (name "unconnected-(ASS_1---Pad2)") (class "Default")
      (node (ref "ASS_1") (pin "2") (pinfunction "-_2") (pintype "input+no_connect"))
    )
    (net (code "54") (name "unconnected-(ASS_2-+-Pad1)") (class "Default")
      (node (ref "ASS_2") (pin "1") (pinfunction "+_1") (pintype "input+no_connect"))
    )
    (net (code "55") (name "unconnected-(ASS_2---Pad2)") (class "Default")
      (node (ref "ASS_2") (pin "2") (pinfunction "-_2") (pintype "input+no_connect"))
    )
    (net (code "56") (name "unconnected-(LDO2-NC-Pad4)") (class "Default")
      (node (ref "LDO2") (pin "4") (pinfunction "NC_4") (pintype "input+no_connect"))
    )
    (net (code "57") (name "unconnected-(SW1-Pad3)") (class "Default")
      (node (ref "SW1") (pin "3") (pinfunction "3_3") (pintype "input+no_connect"))
    )
    (net (code "58") (name "unconnected-(SW1-Pad4)") (class "Default")
      (node (ref "SW1") (pin "4") (pinfunction "4_4") (pintype "input+no_connect"))
    )
    (net (code "59") (name "unconnected-(SW1-Pad5)") (class "Default")
      (node (ref "SW1") (pin "5") (pinfunction "5_5") (pintype "input+no_connect"))
    )
    (net (code "60") (name "unconnected-(U2-AUX_CL-Pad7)") (class "Default")
      (node (ref "U2") (pin "7") (pinfunction "AUX_CL_7") (pintype "input+no_connect"))
    )
    (net (code "61") (name "unconnected-(U2-AUX_DA-Pad6)") (class "Default")
      (node (ref "U2") (pin "6") (pinfunction "AUX_DA_6") (pintype "input+no_connect"))
    )
    (net (code "62") (name "unconnected-(U2-CPOUT-Pad20)") (class "Default")
      (node (ref "U2") (pin "20") (pinfunction "CPOUT_20") (pintype "input+no_connect"))
    )
    (net (code "63") (name "unconnected-(U2-INT-Pad12)") (class "Default")
      (node (ref "U2") (pin "12") (pinfunction "INT_12") (pintype "input+no_connect"))
    )
    (net (code "64") (name "unconnected-(U2-NC-Pad2)") (class "Default")
      (node (ref "U2") (pin "2") (pinfunction "NC_2") (pintype "input+no_connect"))
    )
    (net (code "65") (name "unconnected-(U2-NC-Pad3)") (class "Default")
      (node (ref "U2") (pin "3") (pinfunction "NC_3") (pintype "input+no_connect"))
    )
    (net (code "66") (name "unconnected-(U2-NC-Pad4)") (class "Default")
      (node (ref "U2") (pin "4") (pinfunction "NC_4") (pintype "input+no_connect"))
    )
    (net (code "67") (name "unconnected-(U2-NC-Pad5)") (class "Default")
      (node (ref "U2") (pin "5") (pinfunction "NC_5") (pintype "input+no_connect"))
    )
    (net (code "68") (name "unconnected-(U2-NC-Pad14)") (class "Default")
      (node (ref "U2") (pin "14") (pinfunction "NC_14") (pintype "input+no_connect"))
    )
    (net (code "69") (name "unconnected-(U2-NC-Pad15)") (class "Default")
      (node (ref "U2") (pin "15") (pinfunction "NC_15") (pintype "input+no_connect"))
    )
    (net (code "70") (name "unconnected-(U2-NC-Pad16)") (class "Default")
      (node (ref "U2") (pin "16") (pinfunction "NC_16") (pintype "input+no_connect"))
    )
    (net (code "71") (name "unconnected-(U2-NC-Pad17)") (class "Default")
      (node (ref "U2") (pin "17") (pinfunction "NC_17") (pintype "input+no_connect"))
    )
    (net (code "72") (name "unconnected-(U2-RESV-Pad19)") (class "Default")
      (node (ref "U2") (pin "19") (pinfunction "RESV_19") (pintype "input+no_connect"))
    )
    (net (code "73") (name "unconnected-(U2-RESV-Pad22)") (class "Default")
      (node (ref "U2") (pin "22") (pinfunction "RESV_22") (pintype "input+no_connect"))
    )
    (net (code "74") (name "unconnected-(U3B-(TIM1_CH2N){slash}ADC12_IN8{slash}TIM3_CH3{slash}PB0-Pad18)") (class "Default")
      (node (ref "U3") (pin "18") (pinfunction "(TIM1_CH2N)/ADC12_IN8/TIM3_CH3/PB0_18") (pintype "bidirectional+no_connect"))
    )
    (net (code "75") (name "unconnected-(U3B-(TIM1_CH3N){slash}ADC12_IN9{slash}TIM3_CH4{slash}PB1-Pad19)") (class "Default")
      (node (ref "U3") (pin "19") (pinfunction "(TIM1_CH3N)/ADC12_IN9/TIM3_CH4/PB1_19") (pintype "bidirectional+no_connect"))
    )
    (net (code "76") (name "unconnected-(U3B-(TIM2_CH2{slash}TRACESWO{slash}SPI1_SCK{slash}PB3){slash}JTDO-Pad39)") (class "Default")
      (node (ref "U3") (pin "39") (pinfunction "(TIM2_CH2/TRACESWO/SPI1_SCK/PB3)/JTDO_39") (pintype "bidirectional+no_connect"))
    )
    (net (code "77") (name "unconnected-(U3B-(TIM3_CH1{slash}SPI1_MISO{slash}PB4){slash}JNTRST-Pad40)") (class "Default")
      (node (ref "U3") (pin "40") (pinfunction "(TIM3_CH1/SPI1_MISO/PB4)/JNTRST_40") (pintype "bidirectional+no_connect"))
    )
    (net (code "78") (name "unconnected-(U3B-BOOT1\\PB2-Pad20)") (class "Default")
      (node (ref "U3") (pin "20") (pinfunction "BOOT1\\PB2_20") (pintype "bidirectional+no_connect"))
    )
    (net (code "79") (name "unconnected-(U3B-JTDI{slash}(PA15{slash}TIM2_CH1_ETR{slash}SPI1_NSS)-Pad38)") (class "Default")
      (node (ref "U3") (pin "38") (pinfunction "JTDI/(PA15/TIM2_CH1_ETR/SPI1_NSS)_38") (pintype "bidirectional"))
    )
    (net (code "80") (name "unconnected-(U3B-PA8{slash}USART1_CK{slash}TIM1_CH1{slash}MCO-Pad29)") (class "Default")
      (node (ref "U3") (pin "29") (pinfunction "PA8/USART1_CK/TIM1_CH1/MCO_29") (pintype "bidirectional+no_connect"))
    )
    (net (code "81") (name "unconnected-(U3B-PA12{slash}USART1_RTS{slash}CANTX{slash}USBDP{slash}TIM1_ETR-Pad33)") (class "Default")
      (node (ref "U3") (pin "33") (pinfunction "PA12/USART1_RTS/CANTX/USBDP/TIM1_ETR_33") (pintype "bidirectional"))
    )
    (net (code "82") (name "unconnected-(U3B-PC13{slash}TAMPER-RTC-Pad2)") (class "Default")
      (node (ref "U3") (pin "2") (pinfunction "PC13/TAMPER-RTC_2") (pintype "bidirectional+no_connect"))
    )
    (net (code "83") (name "unconnected-(U3B-PC14{slash}OSC32_IN-Pad3)") (class "Default")
      (node (ref "U3") (pin "3") (pinfunction "PC14/OSC32_IN_3") (pintype "bidirectional+no_connect"))
    )
    (net (code "84") (name "unconnected-(U3B-PC15{slash}OSC32_OUT-Pad4)") (class "Default")
      (node (ref "U3") (pin "4") (pinfunction "PC15/OSC32_OUT_4") (pintype "bidirectional+no_connect"))
    )
    (net (code "85") (name "unconnected-(U3B-SPI2_MISO{slash}USART3_RTS{slash}TIM1_CH2N{slash}PB14-Pad27)") (class "Default")
      (node (ref "U3") (pin "27") (pinfunction "SPI2_MISO/USART3_RTS/TIM1_CH2N/PB14_27") (pintype "bidirectional"))
    )
    (net (code "86") (name "unconnected-(U3B-SPI2_MOSI{slash}TIM1_CH3N{slash}PB15-Pad28)") (class "Default")
      (node (ref "U3") (pin "28") (pinfunction "SPI2_MOSI/TIM1_CH3N/PB15_28") (pintype "bidirectional"))
    )
    (net (code "87") (name "unconnected-(U3B-SPI2_NSS{slash}I2C2_SMBAl{slash}USART3_CK{slash}TIM1_BKIN{slash}PB12-Pad25)") (class "Default")
      (node (ref "U3") (pin "25") (pinfunction "SPI2_NSS/I2C2_SMBAl/USART3_CK/TIM1_BKIN/PB12_25") (pintype "bidirectional+no_connect"))
    )
    (net (code "88") (name "unconnected-(U3B-SPI2_SCK{slash}USART3_CTS{slash}TIM1_CH1N{slash}PB13-Pad26)") (class "Default")
      (node (ref "U3") (pin "26") (pinfunction "SPI2_SCK/USART3_CTS/TIM1_CH1N/PB13_26") (pintype "bidirectional+no_connect"))
    )
  )
)
